# led.net
KiCad netlist of a schematic drawn in EAGLE
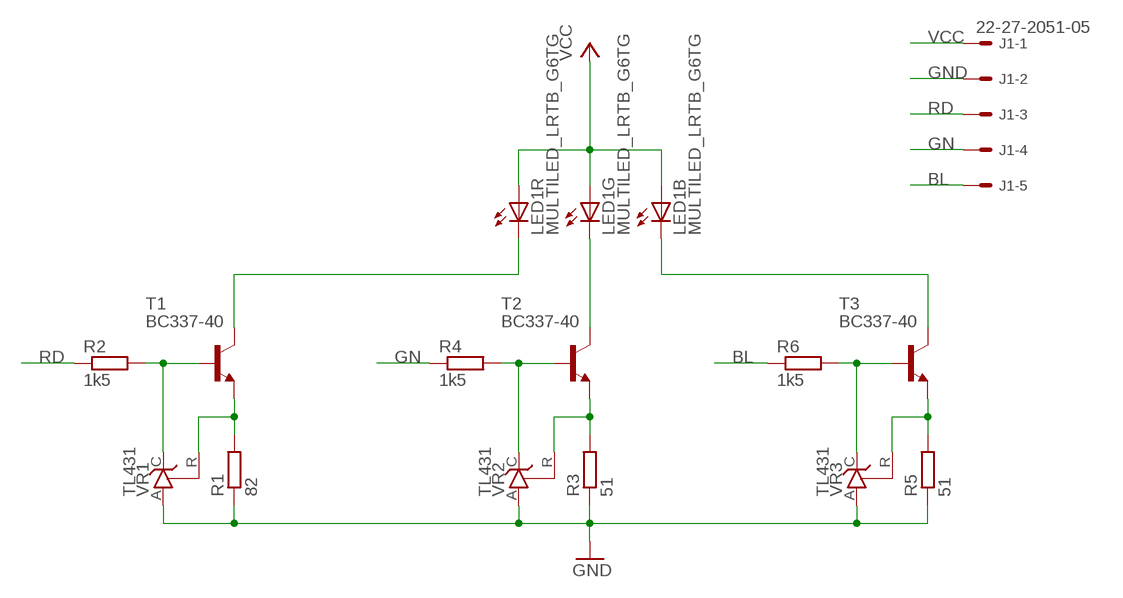
[diagram p0: schematic, sheet 1]

(export (version "E")
  (design (tool "Eeschema 10.0.6"))
  (components
    (comp (ref "J1")
      (value "22-27-2051-05")
      (footprint "eagle-import:6410-05")
      (libsource (lib "eagle-import") (part "22-?-0527-2051"))
    )
    (comp (ref "LED1")
      (value "MULTILED_LRTB_G6TG")
      (footprint "eagle-import:P-LCC-6_TOPLED")
      (libsource (lib "eagle-import") (part "MULTILED_LRTB_G6TG"))
    )
    (comp (ref "R1")
      (value "82")
      (footprint "eagle-import:0207_7")
      (libsource (lib "eagle-import") (part "R-EU_0207/7"))
    )
    (comp (ref "R2")
      (value "1k5")
      (footprint "eagle-import:R0805")
      (libsource (lib "eagle-import") (part "R-EU_R0805"))
    )
    (comp (ref "R3")
      (value "51")
      (footprint "eagle-import:0207_7")
      (libsource (lib "eagle-import") (part "R-EU_0207/7"))
    )
    (comp (ref "R4")
      (value "1k5")
      (footprint "eagle-import:0207_10")
      (libsource (lib "eagle-import") (part "R-EU_0207/10"))
    )
    (comp (ref "R5")
      (value "51")
      (footprint "eagle-import:0207_7")
      (libsource (lib "eagle-import") (part "R-EU_0207/7"))
    )
    (comp (ref "R6")
      (value "1k5")
      (footprint "eagle-import:R0805")
      (libsource (lib "eagle-import") (part "R-EU_R0805"))
    )
    (comp (ref "T1")
      (value "BC337-40")
      (footprint "eagle-import:TO92-CBE")
      (libsource (lib "eagle-import") (part "-NPN-TO92-CBEBC337-40"))
    )
    (comp (ref "T2")
      (value "BC337-40")
      (footprint "eagle-import:TO92-CBE")
      (libsource (lib "eagle-import") (part "-NPN-TO92-CBEBC337-40"))
    )
    (comp (ref "T3")
      (value "BC337-40")
      (footprint "eagle-import:TO92-CBE")
      (libsource (lib "eagle-import") (part "-NPN-TO92-CBEBC337-40"))
    )
    (comp (ref "VR1")
      (value "TL431")
      (footprint "eagle-import:TO92-CLP")
      (libsource (lib "eagle-import") (part "TL431CLP"))
    )
    (comp (ref "VR2")
      (value "TL431")
      (footprint "eagle-import:TO92-CLP")
      (libsource (lib "eagle-import") (part "TL431CLP"))
    )
    (comp (ref "VR3")
      (value "TL431")
      (footprint "eagle-import:TO92-CLP")
      (libsource (lib "eagle-import") (part "TL431CLP"))
    )
  )
  (nets
    (net (code "1") (name "/BL") (class "Default")
      (node (ref "J1") (pin "5") (pinfunction "S_5") (pintype "passive"))
      (node (ref "R6") (pin "1") (pinfunction "1_1") (pintype "passive"))
    )
    (net (code "2") (name "/GN") (class "Default")
      (node (ref "J1") (pin "4") (pinfunction "S_4") (pintype "passive"))
      (node (ref "R4") (pin "1") (pinfunction "1_1") (pintype "passive"))
    )
    (net (code "3") (name "/RD") (class "Default")
      (node (ref "J1") (pin "3") (pinfunction "S_3") (pintype "passive"))
      (node (ref "R2") (pin "1") (pinfunction "1_1") (pintype "passive"))
    )
    (net (code "4") (name "GND") (class "Default")
      (node (ref "J1") (pin "2") (pinfunction "S_2") (pintype "passive"))
      (node (ref "R1") (pin "1") (pinfunction "1_1") (pintype "passive"))
      (node (ref "R3") (pin "1") (pinfunction "1_1") (pintype "passive"))
      (node (ref "R5") (pin "1") (pinfunction "1_1") (pintype "passive"))
      (node (ref "VR1") (pin "A") (pinfunction "A_A") (pintype "passive"))
      (node (ref "VR2") (pin "A") (pinfunction "A_A") (pintype "passive"))
      (node (ref "VR3") (pin "A") (pinfunction "A_A") (pintype "passive"))
    )
    (net (code "5") (name "Net-(LED1A-C)") (class "Default")
      (node (ref "LED1") (pin "C3") (pinfunction "C_C3") (pintype "passive"))
      (node (ref "T3") (pin "C") (pinfunction "C_C") (pintype "passive"))
    )
    (net (code "6") (name "Net-(LED1B-C)") (class "Default")
      (node (ref "LED1") (pin "C2") (pinfunction "C_C2") (pintype "passive"))
      (node (ref "T2") (pin "C") (pinfunction "C_C") (pintype "passive"))
    )
    (net (code "7") (name "Net-(LED1C-C)") (class "Default")
      (node (ref "LED1") (pin "C1") (pinfunction "C_C1") (pintype "passive"))
      (node (ref "T1") (pin "C") (pinfunction "C_C") (pintype "passive"))
    )
    (net (code "8") (name "Net-(R1-Pad2)") (class "Default")
      (node (ref "R1") (pin "2") (pinfunction "2_2") (pintype "passive"))
      (node (ref "T1") (pin "E") (pinfunction "E_E") (pintype "passive"))
      (node (ref "VR1") (pin "R") (pinfunction "R_R") (pintype "passive"))
    )
    (net (code "9") (name "Net-(R2-Pad2)") (class "Default")
      (node (ref "R2") (pin "2") (pinfunction "2_2") (pintype "passive"))
      (node (ref "T1") (pin "B") (pinfunction "B_B") (pintype "passive"))
      (node (ref "VR1") (pin "C") (pinfunction "C_C") (pintype "passive"))
    )
    (net (code "10") (name "Net-(R3-Pad2)") (class "Default")
      (node (ref "R3") (pin "2") (pinfunction "2_2") (pintype "passive"))
      (node (ref "T2") (pin "E") (pinfunction "E_E") (pintype "passive"))
      (node (ref "VR2") (pin "R") (pinfunction "R_R") (pintype "passive"))
    )
    (net (code "11") (name "Net-(R4-Pad2)") (class "Default")
      (node (ref "R4") (pin "2") (pinfunction "2_2") (pintype "passive"))
      (node (ref "T2") (pin "B") (pinfunction "B_B") (pintype "passive"))
      (node (ref "VR2") (pin "C") (pinfunction "C_C") (pintype "passive"))
    )
    (net (code "12") (name "Net-(R5-Pad2)") (class "Default")
      (node (ref "R5") (pin "2") (pinfunction "2_2") (pintype "passive"))
      (node (ref "T3") (pin "E") (pinfunction "E_E") (pintype "passive"))
      (node (ref "VR3") (pin "R") (pinfunction "R_R") (pintype "passive"))
    )
    (net (code "13") (name "Net-(R6-Pad2)") (class "Default")
      (node (ref "R6") (pin "2") (pinfunction "2_2") (pintype "passive"))
      (node (ref "T3") (pin "B") (pinfunction "B_B") (pintype "passive"))
      (node (ref "VR3") (pin "C") (pinfunction "C_C") (pintype "passive"))
    )
    (net (code "14") (name "VCC") (class "Default")
      (node (ref "J1") (pin "1") (pinfunction "S_1") (pintype "passive"))
      (node (ref "LED1") (pin "A1") (pinfunction "A_A1") (pintype "passive"))
      (node (ref "LED1") (pin "A2") (pinfunction "A_A2") (pintype "passive"))
      (node (ref "LED1") (pin "A3") (pinfunction "A_A3") (pintype "passive"))
    )
  )
)
